# Small_robot_PCB_schematic.net
KiCad netlist of a schematic drawn in EAGLE
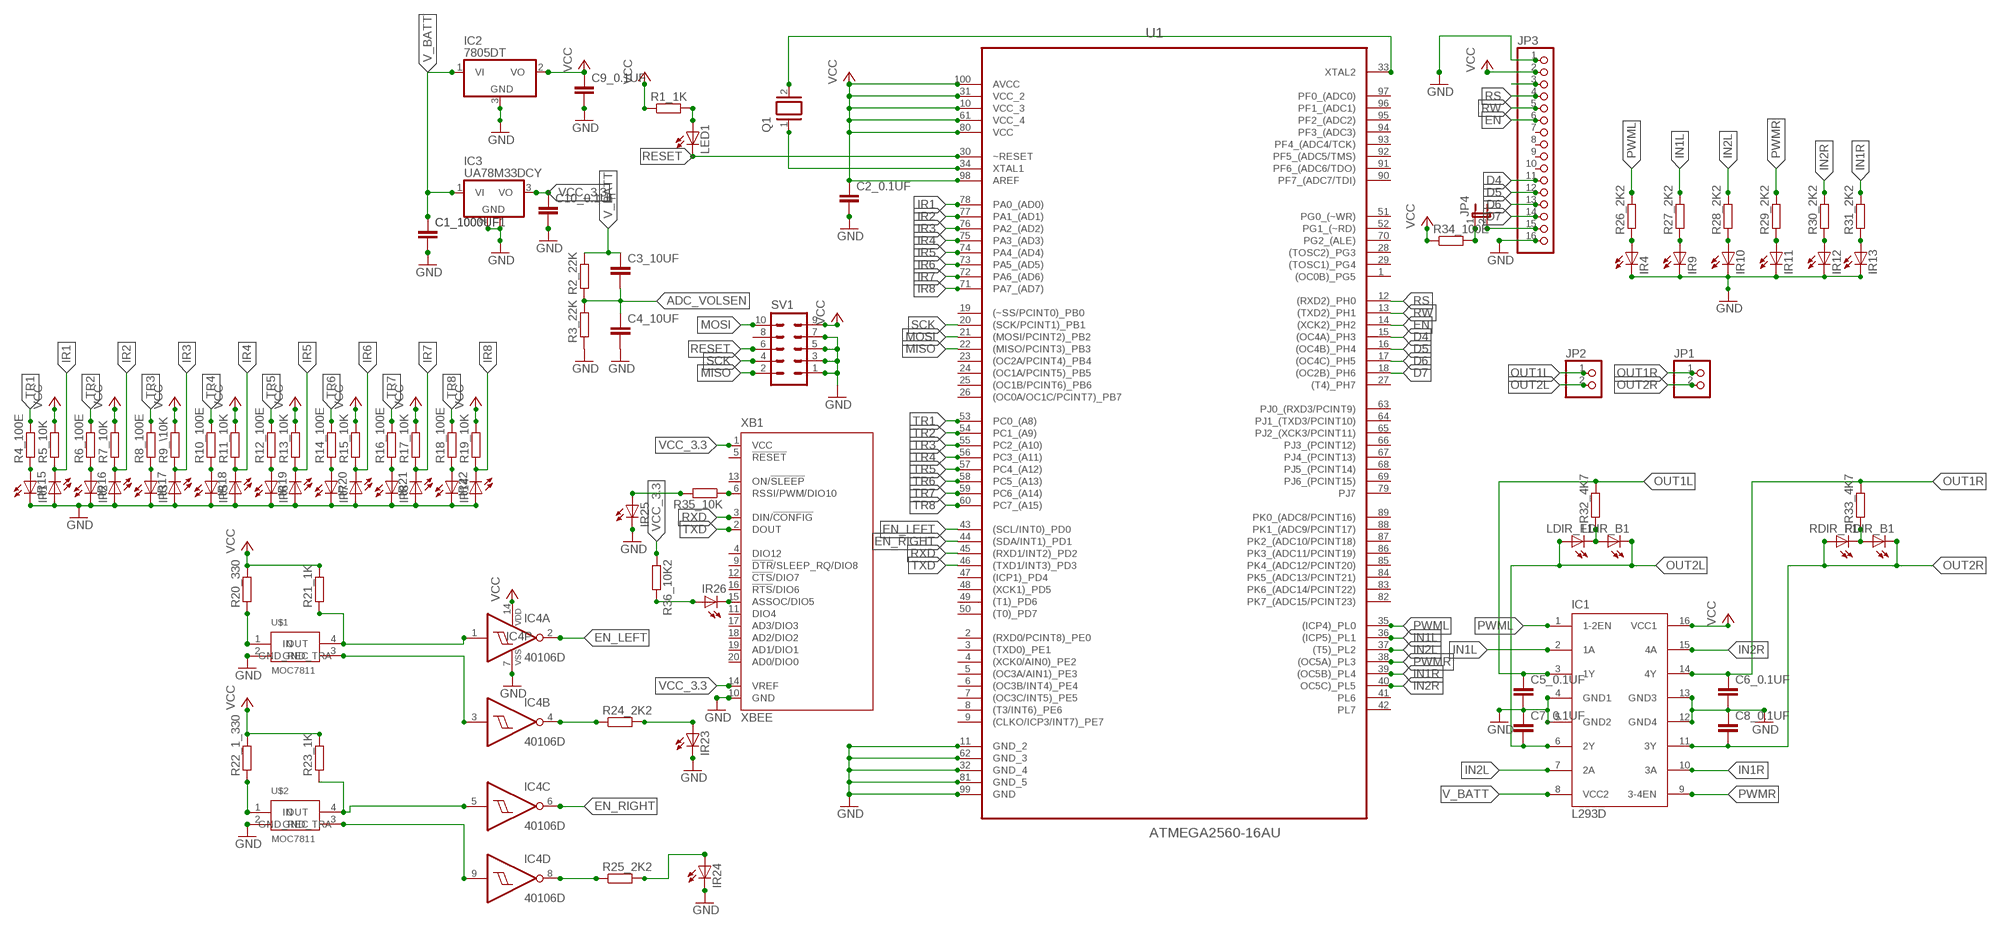
[diagram p0: schematic, sheet 1]

(export (version "E")
  (design (tool "Eeschema 10.0.6"))
  (components
    (comp (ref "C1_1000UF")
      (value "C-EUC1206")
      (footprint "eagle-import:C1206")
      (libsource (lib "eagle-import") (part "resistor_C-EUC1206"))
    )
    (comp (ref "C1_1000UF1")
      (value "C-EUC1206")
      (footprint "eagle-import:C1206")
      (libsource (lib "eagle-import") (part "resistor_C-EUC1206"))
    )
    (comp (ref "C2_0.1UF")
      (value "C-EUC1206")
      (footprint "eagle-import:C1206")
      (libsource (lib "eagle-import") (part "resistor_C-EUC1206"))
    )
    (comp (ref "C3_10UF")
      (value "C-EUC1206")
      (footprint "eagle-import:C1206")
      (libsource (lib "eagle-import") (part "C-EUC1206"))
    )
    (comp (ref "C4_10UF")
      (value "C-EUC1206")
      (footprint "eagle-import:C1206")
      (libsource (lib "eagle-import") (part "C-EUC1206"))
    )
    (comp (ref "C5_0.1UF")
      (value "C-EUC1206")
      (footprint "eagle-import:C1206")
      (libsource (lib "eagle-import") (part "C-EUC1206"))
    )
    (comp (ref "C6_0.1UF")
      (value "C-EUC1206")
      (footprint "eagle-import:C1206")
      (libsource (lib "eagle-import") (part "C-EUC1206"))
    )
    (comp (ref "C7_0.1UF")
      (value "C-EUC1206")
      (footprint "eagle-import:C1206")
      (libsource (lib "eagle-import") (part "C-EUC1206"))
    )
    (comp (ref "C8_0.1UF")
      (value "C-EUC1206")
      (footprint "eagle-import:C1206")
      (libsource (lib "eagle-import") (part "C-EUC1206"))
    )
    (comp (ref "C9_0.1UF")
      (value "C-EUC1206")
      (footprint "eagle-import:C1206")
      (libsource (lib "eagle-import") (part "resistor_C-EUC1206"))
    )
    (comp (ref "C10_0.1UF")
      (value "C-EUC1206")
      (footprint "eagle-import:C1206")
      (libsource (lib "eagle-import") (part "resistor_C-EUC1206"))
    )
    (comp (ref "IC1")
      (value "L293D")
      (footprint "eagle-import:DIL16")
      (libsource (lib "eagle-import") (part "L293D"))
    )
    (comp (ref "IC2")
      (value "7805DT")
      (footprint "eagle-import:TO252")
      (libsource (lib "eagle-import") (part "78DT05"))
    )
    (comp (ref "IC3")
      (value "UA78M33DCY")
      (footprint "eagle-import:SOT223")
      (libsource (lib "eagle-import") (part "UA78MDCY33"))
    )
    (comp (ref "IC4")
      (value "40106D")
      (footprint "eagle-import:SO14")
      (libsource (lib "eagle-import") (part "40106D"))
    )
    (comp (ref "IR1")
      (value "LED5MM")
      (footprint "eagle-import:LED5MM")
      (libsource (lib "eagle-import") (part "LED5MM"))
    )
    (comp (ref "IR2")
      (value "LED5MM")
      (footprint "eagle-import:LED5MM")
      (libsource (lib "eagle-import") (part "LED5MM"))
    )
    (comp (ref "IR3")
      (value "LED5MM")
      (footprint "eagle-import:LED5MM")
      (libsource (lib "eagle-import") (part "LED5MM"))
    )
    (comp (ref "IR4")
      (value "LEDCHIPLED_1206")
      (footprint "eagle-import:CHIPLED_1206")
      (libsource (lib "eagle-import") (part "LEDCHIPLED_1206"))
    )
    (comp (ref "IR5")
      (value "LED5MM")
      (footprint "eagle-import:LED5MM")
      (libsource (lib "eagle-import") (part "LED5MM"))
    )
    (comp (ref "IR6")
      (value "LED5MM")
      (footprint "eagle-import:LED5MM")
      (libsource (lib "eagle-import") (part "LED5MM"))
    )
    (comp (ref "IR7")
      (value "LED5MM")
      (footprint "eagle-import:LED5MM")
      (libsource (lib "eagle-import") (part "LED5MM"))
    )
    (comp (ref "IR8")
      (value "LED5MM")
      (footprint "eagle-import:LED5MM")
      (libsource (lib "eagle-import") (part "LED5MM"))
    )
    (comp (ref "IR9")
      (value "LEDCHIPLED_1206")
      (footprint "eagle-import:CHIPLED_1206")
      (libsource (lib "eagle-import") (part "LEDCHIPLED_1206"))
    )
    (comp (ref "IR10")
      (value "LEDCHIPLED_1206")
      (footprint "eagle-import:CHIPLED_1206")
      (libsource (lib "eagle-import") (part "LEDCHIPLED_1206"))
    )
    (comp (ref "IR11")
      (value "LEDCHIPLED_1206")
      (footprint "eagle-import:CHIPLED_1206")
      (libsource (lib "eagle-import") (part "LEDCHIPLED_1206"))
    )
    (comp (ref "IR12")
      (value "LEDCHIPLED_1206")
      (footprint "eagle-import:CHIPLED_1206")
      (libsource (lib "eagle-import") (part "LEDCHIPLED_1206"))
    )
    (comp (ref "IR13")
      (value "LEDCHIPLED_1206")
      (footprint "eagle-import:CHIPLED_1206")
      (libsource (lib "eagle-import") (part "LEDCHIPLED_1206"))
    )
    (comp (ref "IR14")
      (value "LED5MM")
      (footprint "eagle-import:LED5MM")
      (libsource (lib "eagle-import") (part "LED5MM"))
    )
    (comp (ref "IR15")
      (value "LED5MM")
      (footprint "eagle-import:LED5MM")
      (libsource (lib "eagle-import") (part "LED5MM"))
    )
    (comp (ref "IR16")
      (value "LED5MM")
      (footprint "eagle-import:LED5MM")
      (libsource (lib "eagle-import") (part "LED5MM"))
    )
    (comp (ref "IR17")
      (value "LED5MM")
      (footprint "eagle-import:LED5MM")
      (libsource (lib "eagle-import") (part "LED5MM"))
    )
    (comp (ref "IR18")
      (value "LED5MM")
      (footprint "eagle-import:LED5MM")
      (libsource (lib "eagle-import") (part "LED5MM"))
    )
    (comp (ref "IR19")
      (value "LED5MM")
      (footprint "eagle-import:LED5MM")
      (libsource (lib "eagle-import") (part "LED5MM"))
    )
    (comp (ref "IR20")
      (value "LED5MM")
      (footprint "eagle-import:LED5MM")
      (libsource (lib "eagle-import") (part "LED5MM"))
    )
    (comp (ref "IR21")
      (value "LED5MM")
      (footprint "eagle-import:LED5MM")
      (libsource (lib "eagle-import") (part "LED5MM"))
    )
    (comp (ref "IR22")
      (value "LED5MM")
      (footprint "eagle-import:LED5MM")
      (libsource (lib "eagle-import") (part "LED5MM"))
    )
    (comp (ref "IR23")
      (value "LEDCHIPLED_1206")
      (footprint "eagle-import:CHIPLED_1206")
      (libsource (lib "eagle-import") (part "LEDCHIPLED_1206"))
    )
    (comp (ref "IR24")
      (value "LEDCHIPLED_1206")
      (footprint "eagle-import:CHIPLED_1206")
      (libsource (lib "eagle-import") (part "LEDCHIPLED_1206"))
    )
    (comp (ref "IR25")
      (value "LEDCHIPLED_1206")
      (footprint "eagle-import:CHIPLED_1206")
      (libsource (lib "eagle-import") (part "LEDCHIPLED_1206"))
    )
    (comp (ref "IR26")
      (value "LEDCHIPLED_1206")
      (footprint "eagle-import:CHIPLED_1206")
      (libsource (lib "eagle-import") (part "LEDCHIPLED_1206"))
    )
    (comp (ref "JP1")
      (value "PINHD-1X2")
      (footprint "eagle-import:1X02")
      (libsource (lib "eagle-import") (part "PINHD-1X2"))
    )
    (comp (ref "JP2")
      (value "PINHD-1X2")
      (footprint "eagle-import:1X02")
      (libsource (lib "eagle-import") (part "PINHD-1X2"))
    )
    (comp (ref "JP3")
      (value "PINHD-1X16")
      (footprint "eagle-import:1X16")
      (libsource (lib "eagle-import") (part "PINHD-1X16"))
    )
    (comp (ref "JP4")
      (value "JP1E")
      (footprint "eagle-import:JP1")
      (libsource (lib "eagle-import") (part "JP1E"))
    )
    (comp (ref "LDIR_B1")
      (value "LEDCHIPLED_1206")
      (footprint "eagle-import:CHIPLED_1206")
      (libsource (lib "eagle-import") (part "LEDCHIPLED_1206"))
    )
    (comp (ref "LDIR_F1")
      (value "LEDCHIPLED_1206")
      (footprint "eagle-import:CHIPLED_1206")
      (libsource (lib "eagle-import") (part "LEDCHIPLED_1206"))
    )
    (comp (ref "LED1")
      (value "LEDCHIPLED_1206")
      (footprint "eagle-import:CHIPLED_1206")
      (libsource (lib "eagle-import") (part "LEDCHIPLED_1206"))
    )
    (comp (ref "Q1")
      (value "XTAL")
      (footprint "eagle-import:Q")
      (libsource (lib "eagle-import") (part "XTAL"))
    )
    (comp (ref "R1_1K")
      (value "R-EU_R1206")
      (footprint "eagle-import:R1206")
      (libsource (lib "eagle-import") (part "R-EU_R1206"))
    )
    (comp (ref "R2_22K")
      (value "R-EU_R1206")
      (footprint "eagle-import:R1206")
      (libsource (lib "eagle-import") (part "R-EU_R1206"))
    )
    (comp (ref "R3_22K")
      (value "R-EU_M1206")
      (footprint "eagle-import:M1206")
      (libsource (lib "eagle-import") (part "R-EU_M1206"))
    )
    (comp (ref "R4_100E")
      (value "R-EU_R1206")
      (footprint "eagle-import:R1206")
      (libsource (lib "eagle-import") (part "R-EU_R1206"))
    )
    (comp (ref "R5_10K")
      (value "R-EU_R1206")
      (footprint "eagle-import:R1206")
      (libsource (lib "eagle-import") (part "R-EU_R1206"))
    )
    (comp (ref "R6_100E")
      (value "R-EU_R1206")
      (footprint "eagle-import:R1206")
      (libsource (lib "eagle-import") (part "R-EU_R1206"))
    )
    (comp (ref "R7_10K")
      (value "R-EU_R1206")
      (footprint "eagle-import:R1206")
      (libsource (lib "eagle-import") (part "R-EU_R1206"))
    )
    (comp (ref "R8_100E")
      (value "R-EU_R1206")
      (footprint "eagle-import:R1206")
      (libsource (lib "eagle-import") (part "R-EU_R1206"))
    )
    (comp (ref "R9_\\10K")
      (value "R-EU_R1206")
      (footprint "eagle-import:R1206")
      (libsource (lib "eagle-import") (part "R-EU_R1206"))
    )
    (comp (ref "R10_100E")
      (value "R-EU_R1206")
      (footprint "eagle-import:R1206")
      (libsource (lib "eagle-import") (part "R-EU_R1206"))
    )
    (comp (ref "R11_10K")
      (value "R-EU_R1206")
      (footprint "eagle-import:R1206")
      (libsource (lib "eagle-import") (part "R-EU_R1206"))
    )
    (comp (ref "R12_100E")
      (value "R-EU_R1206")
      (footprint "eagle-import:R1206")
      (libsource (lib "eagle-import") (part "R-EU_R1206"))
    )
    (comp (ref "R13_10K")
      (value "R-EU_R1206")
      (footprint "eagle-import:R1206")
      (libsource (lib "eagle-import") (part "R-EU_R1206"))
    )
    (comp (ref "R14_100E")
      (value "R-EU_R1206")
      (footprint "eagle-import:R1206")
      (libsource (lib "eagle-import") (part "R-EU_R1206"))
    )
    (comp (ref "R15_10K")
      (value "R-EU_R1206")
      (footprint "eagle-import:R1206")
      (libsource (lib "eagle-import") (part "R-EU_R1206"))
    )
    (comp (ref "R16_100E")
      (value "R-EU_R1206")
      (footprint "eagle-import:R1206")
      (libsource (lib "eagle-import") (part "R-EU_R1206"))
    )
    (comp (ref "R17_10K")
      (value "R-EU_R1206")
      (footprint "eagle-import:R1206")
      (libsource (lib "eagle-import") (part "R-EU_R1206"))
    )
    (comp (ref "R18_100E")
      (value "R-EU_R1206")
      (footprint "eagle-import:R1206")
      (libsource (lib "eagle-import") (part "R-EU_R1206"))
    )
    (comp (ref "R19_10K")
      (value "R-EU_R1206")
      (footprint "eagle-import:R1206")
      (libsource (lib "eagle-import") (part "R-EU_R1206"))
    )
    (comp (ref "R20_330")
      (value "R-EU_R1206")
      (footprint "eagle-import:R1206")
      (libsource (lib "eagle-import") (part "R-EU_R1206"))
    )
    (comp (ref "R21_1K")
      (value "R-EU_R1206")
      (footprint "eagle-import:R1206")
      (libsource (lib "eagle-import") (part "R-EU_R1206"))
    )
    (comp (ref "R22_1_330")
      (value "R-EU_R1206")
      (footprint "eagle-import:R1206")
      (libsource (lib "eagle-import") (part "R-EU_R1206"))
    )
    (comp (ref "R23_1K")
      (value "R-EU_R1206")
      (footprint "eagle-import:R1206")
      (libsource (lib "eagle-import") (part "R-EU_R1206"))
    )
    (comp (ref "R24_2K2")
      (value "R-EU_R1206")
      (footprint "eagle-import:R1206")
      (libsource (lib "eagle-import") (part "R-EU_R1206"))
    )
    (comp (ref "R25_2K2")
      (value "R-EU_R1206")
      (footprint "eagle-import:R1206")
      (libsource (lib "eagle-import") (part "R-EU_R1206"))
    )
    (comp (ref "R26_2K2")
      (value "R-EU_R1206")
      (footprint "eagle-import:R1206")
      (libsource (lib "eagle-import") (part "R-EU_R1206"))
    )
    (comp (ref "R27_2K2")
      (value "R-EU_R1206")
      (footprint "eagle-import:R1206")
      (libsource (lib "eagle-import") (part "R-EU_R1206"))
    )
    (comp (ref "R28_2K2")
      (value "R-EU_R1206")
      (footprint "eagle-import:R1206")
      (libsource (lib "eagle-import") (part "R-EU_R1206"))
    )
    (comp (ref "R29_2K2")
      (value "R-EU_R1206")
      (footprint "eagle-import:R1206")
      (libsource (lib "eagle-import") (part "R-EU_R1206"))
    )
    (comp (ref "R30_2K2")
      (value "R-EU_R1206")
      (footprint "eagle-import:R1206")
      (libsource (lib "eagle-import") (part "R-EU_R1206"))
    )
    (comp (ref "R31_2K2")
      (value "R-EU_R1206")
      (footprint "eagle-import:R1206")
      (libsource (lib "eagle-import") (part "R-EU_R1206"))
    )
    (comp (ref "R32_4K7")
      (value "R-EU_R1206")
      (footprint "eagle-import:R1206")
      (libsource (lib "eagle-import") (part "R-EU_R1206"))
    )
    (comp (ref "R33_4K7")
      (value "R-EU_R1206")
      (footprint "eagle-import:R1206")
      (libsource (lib "eagle-import") (part "R-EU_R1206"))
    )
    (comp (ref "R34_100E")
      (value "R-EU_R1206")
      (footprint "eagle-import:R1206")
      (libsource (lib "eagle-import") (part "R-EU_R1206"))
    )
    (comp (ref "R35_10K")
      (value "R-EU_R1206")
      (footprint "eagle-import:R1206")
      (libsource (lib "eagle-import") (part "R-EU_R1206"))
    )
    (comp (ref "R36_10K2")
      (value "R-EU_R1206")
      (footprint "eagle-import:R1206")
      (libsource (lib "eagle-import") (part "R-EU_R1206"))
    )
    (comp (ref "RDIR_B1")
      (value "LEDCHIPLED_1206")
      (footprint "eagle-import:CHIPLED_1206")
      (libsource (lib "eagle-import") (part "LEDCHIPLED_1206"))
    )
    (comp (ref "RDIR_F1")
      (value "LEDCHIPLED_1206")
      (footprint "eagle-import:CHIPLED_1206")
      (libsource (lib "eagle-import") (part "LEDCHIPLED_1206"))
    )
    (comp (ref "SV1")
      (value "MA05-2")
      (footprint "eagle-import:MA05-2")
      (libsource (lib "eagle-import") (part "MA05-2"))
    )
    (comp (ref "U$1")
      (value "MOC7811")
      (footprint "eagle-import:THROUGH_HOLE_NORMAL")
      (libsource (lib "eagle-import") (part "MOC7811"))
    )
    (comp (ref "U$2")
      (value "MOC7811")
      (footprint "eagle-import:THROUGH_HOLE_NORMAL")
      (libsource (lib "eagle-import") (part "MOC7811"))
    )
    (comp (ref "U1")
      (value "ATMEGA2560-16AU")
      (footprint "eagle-import:QFP50P1600X1600X120-100N")
      (libsource (lib "eagle-import") (part "ATMEGA2560-16AU"))
    )
    (comp (ref "XB1")
      (value "XBEE")
      (footprint "eagle-import:XBEE")
      (fields (field (name "MPN") "XBP24-Z7UIT-004"))
      (libsource (lib "eagle-import") (part "XBEE"))
    )
  )
  (nets
    (net (code "1") (name "ADC_VOLSEN") (class "Default")
      (node (ref "C3_10UF") (pin "2") (pinfunction "2_2") (pintype "passive"))
      (node (ref "C4_10UF") (pin "1") (pinfunction "1_1") (pintype "passive"))
      (node (ref "R2_22K") (pin "1") (pinfunction "1_1") (pintype "passive"))
      (node (ref "R3_22K") (pin "2") (pinfunction "2_2") (pintype "passive"))
    )
    (net (code "2") (name "D4") (class "Default")
      (node (ref "JP3") (pin "11") (pinfunction "11_11") (pintype "passive"))
      (node (ref "U1") (pin "15") (pinfunction "(OC4A)_PH3_15") (pintype "bidirectional"))
    )
    (net (code "3") (name "D5") (class "Default")
      (node (ref "JP3") (pin "12") (pinfunction "12_12") (pintype "passive"))
      (node (ref "U1") (pin "16") (pinfunction "(OC4B)_PH4_16") (pintype "bidirectional"))
    )
    (net (code "4") (name "D6") (class "Default")
      (node (ref "JP3") (pin "13") (pinfunction "13_13") (pintype "passive"))
      (node (ref "U1") (pin "17") (pinfunction "(OC4C)_PH5_17") (pintype "bidirectional"))
    )
    (net (code "5") (name "D7") (class "Default")
      (node (ref "JP3") (pin "14") (pinfunction "14_14") (pintype "passive"))
      (node (ref "U1") (pin "18") (pinfunction "(OC2B)_PH6_18") (pintype "bidirectional"))
    )
    (net (code "6") (name "EN") (class "Default")
      (node (ref "JP3") (pin "6") (pinfunction "6_6") (pintype "passive"))
      (node (ref "U1") (pin "14") (pinfunction "(XCK2)_PH2_14") (pintype "bidirectional"))
    )
    (net (code "7") (name "EN_LEFT") (class "Default")
      (node (ref "IC4") (pin "2") (pinfunction "O_2") (pintype "output"))
      (node (ref "U1") (pin "43") (pinfunction "(SCL/INT0)_PD0_43") (pintype "bidirectional"))
    )
    (net (code "8") (name "EN_RIGHT") (class "Default")
      (node (ref "IC4") (pin "6") (pinfunction "O_6") (pintype "output"))
      (node (ref "U1") (pin "44") (pinfunction "(SDA/INT1)_PD1_44") (pintype "bidirectional"))
    )
    (net (code "9") (name "GND") (class "Default")
      (node (ref "C10_0.1UF") (pin "2") (pinfunction "2_2") (pintype "passive"))
      (node (ref "C1_1000UF") (pin "2") (pinfunction "2_2") (pintype "passive"))
      (node (ref "C1_1000UF1") (pin "2") (pinfunction "2_2") (pintype "passive"))
      (node (ref "C2_0.1UF") (pin "2") (pinfunction "2_2") (pintype "passive"))
      (node (ref "C4_10UF") (pin "2") (pinfunction "2_2") (pintype "passive"))
      (node (ref "C5_0.1UF") (pin "2") (pinfunction "2_2") (pintype "passive"))
      (node (ref "C6_0.1UF") (pin "2") (pinfunction "2_2") (pintype "passive"))
      (node (ref "C7_0.1UF") (pin "1") (pinfunction "1_1") (pintype "passive"))
      (node (ref "C8_0.1UF") (pin "1") (pinfunction "1_1") (pintype "passive"))
      (node (ref "C9_0.1UF") (pin "2") (pinfunction "2_2") (pintype "passive"))
      (node (ref "IC1") (pin "12") (pinfunction "GND4_12") (pintype "power_in"))
      (node (ref "IC1") (pin "13") (pinfunction "GND3_13") (pintype "power_in"))
      (node (ref "IC1") (pin "4") (pinfunction "GND1_4") (pintype "power_in"))
      (node (ref "IC1") (pin "5") (pinfunction "GND2_5") (pintype "power_in"))
      (node (ref "IC2") (pin "3") (pinfunction "GND_3") (pintype "passive"))
      (node (ref "IC3") (pin "2") (pinfunction "GND_2") (pintype "passive"))
      (node (ref "IC3") (pin "4") (pinfunction "GND_4") (pintype "passive"))
      (node (ref "IC4") (pin "7") (pinfunction "VSS_7") (pintype "power_in"))
      (node (ref "IR1") (pin "K") (pinfunction "C_K") (pintype "passive"))
      (node (ref "IR10") (pin "C") (pinfunction "C_C") (pintype "passive"))
      (node (ref "IR11") (pin "C") (pinfunction "C_C") (pintype "passive"))
      (node (ref "IR12") (pin "C") (pinfunction "C_C") (pintype "passive"))
      (node (ref "IR13") (pin "C") (pinfunction "C_C") (pintype "passive"))
      (node (ref "IR14") (pin "K") (pinfunction "C_K") (pintype "passive"))
      (node (ref "IR15") (pin "A") (pinfunction "A_A") (pintype "passive"))
      (node (ref "IR16") (pin "A") (pinfunction "A_A") (pintype "passive"))
      (node (ref "IR17") (pin "A") (pinfunction "A_A") (pintype "passive"))
      (node (ref "IR18") (pin "A") (pinfunction "A_A") (pintype "passive"))
      (node (ref "IR19") (pin "A") (pinfunction "A_A") (pintype "passive"))
      (node (ref "IR2") (pin "K") (pinfunction "C_K") (pintype "passive"))
      (node (ref "IR20") (pin "A") (pinfunction "A_A") (pintype "passive"))
      (node (ref "IR21") (pin "A") (pinfunction "A_A") (pintype "passive"))
      (node (ref "IR22") (pin "A") (pinfunction "A_A") (pintype "passive"))
      (node (ref "IR23") (pin "C") (pinfunction "C_C") (pintype "passive"))
      (node (ref "IR24") (pin "C") (pinfunction "C_C") (pintype "passive"))
      (node (ref "IR25") (pin "C") (pinfunction "C_C") (pintype "passive"))
      (node (ref "IR3") (pin "K") (pinfunction "C_K") (pintype "passive"))
      (node (ref "IR4") (pin "C") (pinfunction "C_C") (pintype "passive"))
      (node (ref "IR5") (pin "K") (pinfunction "C_K") (pintype "passive"))
      (node (ref "IR6") (pin "K") (pinfunction "C_K") (pintype "passive"))
      (node (ref "IR7") (pin "K") (pinfunction "C_K") (pintype "passive"))
      (node (ref "IR8") (pin "K") (pinfunction "C_K") (pintype "passive"))
      (node (ref "IR9") (pin "C") (pinfunction "C_C") (pintype "passive"))
      (node (ref "JP3") (pin "1") (pinfunction "1_1") (pintype "passive"))
      (node (ref "JP3") (pin "16") (pinfunction "16_16") (pintype "passive"))
      (node (ref "R3_22K") (pin "1") (pinfunction "1_1") (pintype "passive"))
      (node (ref "SV1") (pin "1") (pinfunction "1_1") (pintype "passive"))
      (node (ref "SV1") (pin "3") (pinfunction "3_3") (pintype "passive"))
      (node (ref "SV1") (pin "5") (pinfunction "5_5") (pintype "passive"))
      (node (ref "SV1") (pin "7") (pinfunction "7_7") (pintype "passive"))
      (node (ref "U$1") (pin "2") (pinfunction "GND_TRA_2") (pintype "bidirectional"))
      (node (ref "U$2") (pin "2") (pinfunction "GND_TRA_2") (pintype "bidirectional"))
      (node (ref "U1") (pin "11") (pinfunction "GND_2_11") (pintype "passive"))
      (node (ref "U1") (pin "32") (pinfunction "GND_4_32") (pintype "passive"))
      (node (ref "U1") (pin "62") (pinfunction "GND_3_62") (pintype "passive"))
      (node (ref "U1") (pin "81") (pinfunction "GND_5_81") (pintype "passive"))
      (node (ref "U1") (pin "99") (pinfunction "GND_99") (pintype "passive"))
      (node (ref "XB1") (pin "10") (pinfunction "GND_10") (pintype "power_in"))
    )
    (net (code "10") (name "IN1L") (class "Default")
      (node (ref "IC1") (pin "2") (pinfunction "1A_2") (pintype "input"))
      (node (ref "R27_2K2") (pin "2") (pinfunction "2_2") (pintype "passive"))
      (node (ref "U1") (pin "36") (pinfunction "(ICP5)_PL1_36") (pintype "bidirectional"))
    )
    (net (code "11") (name "IN1R") (class "Default")
      (node (ref "IC1") (pin "10") (pinfunction "3A_10") (pintype "input"))
      (node (ref "R31_2K2") (pin "2") (pinfunction "2_2") (pintype "passive"))
      (node (ref "U1") (pin "39") (pinfunction "(OC5B)_PL4_39") (pintype "bidirectional"))
    )
    (net (code "12") (name "IN2L") (class "Default")
      (node (ref "IC1") (pin "7") (pinfunction "2A_7") (pintype "input"))
      (node (ref "R28_2K2") (pin "2") (pinfunction "2_2") (pintype "passive"))
      (node (ref "U1") (pin "37") (pinfunction "(T5)_PL2_37") (pintype "bidirectional"))
    )
    (net (code "13") (name "IN2R") (class "Default")
      (node (ref "IC1") (pin "15") (pinfunction "4A_15") (pintype "input"))
      (node (ref "R30_2K2") (pin "2") (pinfunction "2_2") (pintype "passive"))
      (node (ref "U1") (pin "40") (pinfunction "OC5C)_PL5_40") (pintype "bidirectional"))
    )
    (net (code "14") (name "IR1") (class "Default")
      (node (ref "IR15") (pin "K") (pinfunction "C_K") (pintype "passive"))
      (node (ref "R5_10K") (pin "1") (pinfunction "1_1") (pintype "passive"))
      (node (ref "U1") (pin "78") (pinfunction "PA0_(AD0)_78") (pintype "bidirectional"))
    )
    (net (code "15") (name "IR2") (class "Default")
      (node (ref "IR16") (pin "K") (pinfunction "C_K") (pintype "passive"))
      (node (ref "R7_10K") (pin "1") (pinfunction "1_1") (pintype "passive"))
      (node (ref "U1") (pin "77") (pinfunction "PA1_(AD1)_77") (pintype "bidirectional"))
    )
    (net (code "16") (name "IR3") (class "Default")
      (node (ref "IR17") (pin "K") (pinfunction "C_K") (pintype "passive"))
      (node (ref "R9_\\10K") (pin "1") (pinfunction "1_1") (pintype "passive"))
      (node (ref "U1") (pin "76") (pinfunction "PA2_(AD2)_76") (pintype "bidirectional"))
    )
    (net (code "17") (name "IR4") (class "Default")
      (node (ref "IR18") (pin "K") (pinfunction "C_K") (pintype "passive"))
      (node (ref "R11_10K") (pin "1") (pinfunction "1_1") (pintype "passive"))
      (node (ref "U1") (pin "75") (pinfunction "PA3_(AD3)_75") (pintype "bidirectional"))
    )
    (net (code "18") (name "IR5") (class "Default")
      (node (ref "IR19") (pin "K") (pinfunction "C_K") (pintype "passive"))
      (node (ref "R13_10K") (pin "1") (pinfunction "1_1") (pintype "passive"))
      (node (ref "U1") (pin "74") (pinfunction "PA4_(AD4)_74") (pintype "bidirectional"))
    )
    (net (code "19") (name "IR6") (class "Default")
      (node (ref "IR20") (pin "K") (pinfunction "C_K") (pintype "passive"))
      (node (ref "R15_10K") (pin "1") (pinfunction "1_1") (pintype "passive"))
      (node (ref "U1") (pin "73") (pinfunction "PA5_(AD5)_73") (pintype "bidirectional"))
    )
    (net (code "20") (name "IR7") (class "Default")
      (node (ref "IR21") (pin "K") (pinfunction "C_K") (pintype "passive"))
      (node (ref "R17_10K") (pin "1") (pinfunction "1_1") (pintype "passive"))
      (node (ref "U1") (pin "72") (pinfunction "PA6_(AD6)_72") (pintype "bidirectional"))
    )
    (net (code "21") (name "IR8") (class "Default")
      (node (ref "IR22") (pin "K") (pinfunction "C_K") (pintype "passive"))
      (node (ref "R19_10K") (pin "1") (pinfunction "1_1") (pintype "passive"))
      (node (ref "U1") (pin "71") (pinfunction "PA7_(AD7)_71") (pintype "bidirectional"))
    )
    (net (code "22") (name "MISO") (class "Default")
      (node (ref "SV1") (pin "2") (pinfunction "2_2") (pintype "passive"))
      (node (ref "U1") (pin "22") (pinfunction "(MISO/PCINT3)_PB3_22") (pintype "bidirectional"))
    )
    (net (code "23") (name "MOSI") (class "Default")
      (node (ref "SV1") (pin "10") (pinfunction "10_10") (pintype "passive"))
      (node (ref "U1") (pin "21") (pinfunction "(MOSI/PCINT2)_PB2_21") (pintype "bidirectional"))
    )
    (net (code "24") (name "Net-(IC4A-I)") (class "Default")
      (node (ref "IC4") (pin "1") (pinfunction "I_1") (pintype "input"))
      (node (ref "R21_1K") (pin "1") (pinfunction "1_1") (pintype "passive"))
      (node (ref "U$1") (pin "4") (pinfunction "OUT_4") (pintype "bidirectional"))
    )
    (net (code "25") (name "Net-(IC4B-I)") (class "Default")
      (node (ref "IC4") (pin "3") (pinfunction "I_3") (pintype "input"))
      (node (ref "U$1") (pin "3") (pinfunction "GND_REC_3") (pintype "bidirectional"))
    )
    (net (code "26") (name "Net-(IC4B-O)") (class "Default")
      (node (ref "IC4") (pin "4") (pinfunction "O_4") (pintype "output"))
      (node (ref "R24_2K2") (pin "1") (pinfunction "1_1") (pintype "passive"))
    )
    (net (code "27") (name "Net-(IC4C-I)") (class "Default")
      (node (ref "IC4") (pin "5") (pinfunction "I_5") (pintype "input"))
      (node (ref "R23_1K") (pin "1") (pinfunction "1_1") (pintype "passive"))
      (node (ref "U$2") (pin "4") (pinfunction "OUT_4") (pintype "bidirectional"))
    )
    (net (code "28") (name "Net-(IC4D-I)") (class "Default")
      (node (ref "IC4") (pin "9") (pinfunction "I_9") (pintype "input"))
      (node (ref "U$2") (pin "3") (pinfunction "GND_REC_3") (pintype "bidirectional"))
    )
    (net (code "29") (name "Net-(IC4D-O)") (class "Default")
      (node (ref "IC4") (pin "8") (pinfunction "O_8") (pintype "output"))
      (node (ref "R25_2K2") (pin "1") (pinfunction "1_1") (pintype "passive"))
    )
    (net (code "30") (name "Net-(IR1-PadA)") (class "Default")
      (node (ref "IR1") (pin "A") (pinfunction "A_A") (pintype "passive"))
      (node (ref "R4_100E") (pin "1") (pinfunction "1_1") (pintype "passive"))
    )
    (net (code "31") (name "Net-(IR2-PadA)") (class "Default")
      (node (ref "IR2") (pin "A") (pinfunction "A_A") (pintype "passive"))
      (node (ref "R6_100E") (pin "1") (pinfunction "1_1") (pintype "passive"))
    )
    (net (code "32") (name "Net-(IR3-PadA)") (class "Default")
      (node (ref "IR3") (pin "A") (pinfunction "A_A") (pintype "passive"))
      (node (ref "R8_100E") (pin "1") (pinfunction "1_1") (pintype "passive"))
    )
    (net (code "33") (name "Net-(IR4-PadA)") (class "Default")
      (node (ref "IR4") (pin "A") (pinfunction "A_A") (pintype "passive"))
      (node (ref "R26_2K2") (pin "1") (pinfunction "1_1") (pintype "passive"))
    )
    (net (code "34") (name "Net-(IR5-PadA)") (class "Default")
      (node (ref "IR5") (pin "A") (pinfunction "A_A") (pintype "passive"))
      (node (ref "R10_100E") (pin "1") (pinfunction "1_1") (pintype "passive"))
    )
    (net (code "35") (name "Net-(IR6-PadA)") (class "Default")
      (node (ref "IR6") (pin "A") (pinfunction "A_A") (pintype "passive"))
      (node (ref "R12_100E") (pin "1") (pinfunction "1_1") (pintype "passive"))
    )
    (net (code "36") (name "Net-(IR7-PadA)") (class "Default")
      (node (ref "IR7") (pin "A") (pinfunction "A_A") (pintype "passive"))
      (node (ref "R14_100E") (pin "1") (pinfunction "1_1") (pintype "passive"))
    )
    (net (code "37") (name "Net-(IR8-PadA)") (class "Default")
      (node (ref "IR8") (pin "A") (pinfunction "A_A") (pintype "passive"))
      (node (ref "R16_100E") (pin "1") (pinfunction "1_1") (pintype "passive"))
    )
    (net (code "38") (name "Net-(IR9-PadA)") (class "Default")
      (node (ref "IR9") (pin "A") (pinfunction "A_A") (pintype "passive"))
      (node (ref "R27_2K2") (pin "1") (pinfunction "1_1") (pintype "passive"))
    )
    (net (code "39") (name "Net-(IR10-PadA)") (class "Default")
      (node (ref "IR10") (pin "A") (pinfunction "A_A") (pintype "passive"))
      (node (ref "R28_2K2") (pin "1") (pinfunction "1_1") (pintype "passive"))
    )
    (net (code "40") (name "Net-(IR11-PadA)") (class "Default")
      (node (ref "IR11") (pin "A") (pinfunction "A_A") (pintype "passive"))
      (node (ref "R29_2K2") (pin "1") (pinfunction "1_1") (pintype "passive"))
    )
    (net (code "41") (name "Net-(IR12-PadA)") (class "Default")
      (node (ref "IR12") (pin "A") (pinfunction "A_A") (pintype "passive"))
      (node (ref "R30_2K2") (pin "1") (pinfunction "1_1") (pintype "passive"))
    )
    (net (code "42") (name "Net-(IR13-PadA)") (class "Default")
      (node (ref "IR13") (pin "A") (pinfunction "A_A") (pintype "passive"))
      (node (ref "R31_2K2") (pin "1") (pinfunction "1_1") (pintype "passive"))
    )
    (net (code "43") (name "Net-(IR14-PadA)") (class "Default")
      (node (ref "IR14") (pin "A") (pinfunction "A_A") (pintype "passive"))
      (node (ref "R18_100E") (pin "1") (pinfunction "1_1") (pintype "passive"))
    )
    (net (code "44") (name "Net-(IR23-PadA)") (class "Default")
      (node (ref "IR23") (pin "A") (pinfunction "A_A") (pintype "passive"))
      (node (ref "R24_2K2") (pin "2") (pinfunction "2_2") (pintype "passive"))
    )
    (net (code "45") (name "Net-(IR24-PadA)") (class "Default")
      (node (ref "IR24") (pin "A") (pinfunction "A_A") (pintype "passive"))
      (node (ref "R25_2K2") (pin "2") (pinfunction "2_2") (pintype "passive"))
    )
    (net (code "46") (name "Net-(IR25-PadA)") (class "Default")
      (node (ref "IR25") (pin "A") (pinfunction "A_A") (pintype "passive"))
      (node (ref "R35_10K") (pin "2") (pinfunction "2_2") (pintype "passive"))
    )
    (net (code "47") (name "Net-(IR26-PadA)") (class "Default")
      (node (ref "IR26") (pin "A") (pinfunction "A_A") (pintype "passive"))
      (node (ref "R36_10K2") (pin "2") (pinfunction "2_2") (pintype "passive"))
    )
    (net (code "48") (name "Net-(JP3-Pad15)") (class "Default")
      (node (ref "JP3") (pin "15") (pinfunction "15_15") (pintype "passive"))
      (node (ref "JP4") (pin "2") (pinfunction "2_2") (pintype "passive"))
    )
    (net (code "49") (name "Net-(JP4-Pad1)") (class "Default")
      (node (ref "JP4") (pin "1") (pinfunction "1_1") (pintype "passive"))
      (node (ref "R34_100E") (pin "2") (pinfunction "2_2") (pintype "passive"))
    )
    (net (code "50") (name "Net-(LDIR_B1-PadA)") (class "Default")
      (node (ref "LDIR_B1") (pin "A") (pinfunction "A_A") (pintype "passive"))
      (node (ref "LDIR_F1") (pin "C") (pinfunction "C_C") (pintype "passive"))
      (node (ref "R32_4K7") (pin "1") (pinfunction "1_1") (pintype "passive"))
    )
    (net (code "51") (name "Net-(LED1-PadA)") (class "Default")
      (node (ref "LED1") (pin "A") (pinfunction "A_A") (pintype "passive"))
      (node (ref "R1_1K") (pin "2") (pinfunction "2_2") (pintype "passive"))
    )
    (net (code "52") (name "Net-(R33_4K7-Pad1)") (class "Default")
      (node (ref "R33_4K7") (pin "1") (pinfunction "1_1") (pintype "passive"))
      (node (ref "RDIR_B1") (pin "A") (pinfunction "A_A") (pintype "passive"))
      (node (ref "RDIR_F1") (pin "C") (pinfunction "C_C") (pintype "passive"))
    )
    (net (code "53") (name "Net-(U$1-IN)") (class "Default")
      (node (ref "R20_330") (pin "1") (pinfunction "1_1") (pintype "passive"))
      (node (ref "U$1") (pin "1") (pinfunction "IN_1") (pintype "bidirectional"))
    )
    (net (code "54") (name "Net-(U$2-IN)") (class "Default")
      (node (ref "R22_1_330") (pin "1") (pinfunction "1_1") (pintype "passive"))
      (node (ref "U$2") (pin "1") (pinfunction "IN_1") (pintype "bidirectional"))
    )
    (net (code "55") (name "Net-(U1-XTAL1)") (class "Default")
      (node (ref "Q1") (pin "1") (pinfunction "1_1") (pintype "passive"))
      (node (ref "U1") (pin "34") (pinfunction "XTAL1_34") (pintype "input"))
    )
    (net (code "56") (name "Net-(U1-XTAL2)") (class "Default")
      (node (ref "Q1") (pin "2") (pinfunction "2_2") (pintype "passive"))
      (node (ref "U1") (pin "33") (pinfunction "XTAL2_33") (pintype "output"))
    )
    (net (code "57") (name "Net-(XB1-ASSOC{slash}DIO5)") (class "Default")
      (node (ref "IR26") (pin "C") (pinfunction "C_C") (pintype "passive"))
      (node (ref "XB1") (pin "15") (pinfunction "ASSOC/DIO5_15") (pintype "bidirectional"))
    )
    (net (code "58") (name "Net-(XB1-RSSI{slash}PWM{slash}DIO10)") (class "Default")
      (node (ref "R35_10K") (pin "1") (pinfunction "1_1") (pintype "passive"))
      (node (ref "XB1") (pin "6") (pinfunction "RSSI/PWM/DIO10_6") (pintype "output"))
    )
    (net (code "59") (name "OUT1L") (class "Default")
      (node (ref "C5_0.1UF") (pin "1") (pinfunction "1_1") (pintype "passive"))
      (node (ref "IC1") (pin "3") (pinfunction "1Y_3") (pintype "output"))
      (node (ref "JP2") (pin "1") (pinfunction "1_1") (pintype "passive"))
      (node (ref "R32_4K7") (pin "2") (pinfunction "2_2") (pintype "passive"))
    )
    (net (code "60") (name "OUT1R") (class "Default")
      (node (ref "C6_0.1UF") (pin "1") (pinfunction "1_1") (pintype "passive"))
      (node (ref "IC1") (pin "14") (pinfunction "4Y_14") (pintype "output"))
      (node (ref "JP1") (pin "1") (pinfunction "1_1") (pintype "passive"))
      (node (ref "R33_4K7") (pin "2") (pinfunction "2_2") (pintype "passive"))
    )
    (net (code "61") (name "OUT2L") (class "Default")
      (node (ref "C7_0.1UF") (pin "2") (pinfunction "2_2") (pintype "passive"))
      (node (ref "IC1") (pin "6") (pinfunction "2Y_6") (pintype "output"))
      (node (ref "JP2") (pin "2") (pinfunction "2_2") (pintype "passive"))
      (node (ref "LDIR_B1") (pin "C") (pinfunction "C_C") (pintype "passive"))
      (node (ref "LDIR_F1") (pin "A") (pinfunction "A_A") (pintype "passive"))
    )
    (net (code "62") (name "OUT2R") (class "Default")
      (node (ref "C8_0.1UF") (pin "2") (pinfunction "2_2") (pintype "passive"))
      (node (ref "IC1") (pin "11") (pinfunction "3Y_11") (pintype "output"))
      (node (ref "JP1") (pin "2") (pinfunction "2_2") (pintype "passive"))
      (node (ref "RDIR_B1") (pin "C") (pinfunction "C_C") (pintype "passive"))
      (node (ref "RDIR_F1") (pin "A") (pinfunction "A_A") (pintype "passive"))
    )
    (net (code "63") (name "PWML") (class "Default")
      (node (ref "IC1") (pin "1") (pinfunction "1-2EN_1") (pintype "input"))
      (node (ref "R26_2K2") (pin "2") (pinfunction "2_2") (pintype "passive"))
      (node (ref "U1") (pin "35") (pinfunction "(ICP4)_PL0_35") (pintype "bidirectional"))
    )
    (net (code "64") (name "PWMR") (class "Default")
      (node (ref "IC1") (pin "9") (pinfunction "3-4EN_9") (pintype "input"))
      (node (ref "R29_2K2") (pin "2") (pinfunction "2_2") (pintype "passive"))
      (node (ref "U1") (pin "38") (pinfunction "(OC5A)_PL3_38") (pintype "bidirectional"))
    )
    (net (code "65") (name "RESET") (class "Default")
      (node (ref "LED1") (pin "C") (pinfunction "C_C") (pintype "passive"))
      (node (ref "SV1") (pin "6") (pinfunction "6_6") (pintype "passive"))
      (node (ref "U1") (pin "30") (pinfunction "~{RESET}_30") (pintype "input"))
    )
    (net (code "66") (name "RS") (class "Default")
      (node (ref "JP3") (pin "4") (pinfunction "4_4") (pintype "passive"))
      (node (ref "U1") (pin "12") (pinfunction "(RXD2)_PH0_12") (pintype "bidirectional"))
    )
    (net (code "67") (name "RW") (class "Default")
      (node (ref "JP3") (pin "5") (pinfunction "5_5") (pintype "passive"))
      (node (ref "U1") (pin "13") (pinfunction "(TXD2)_PH1_13") (pintype "bidirectional"))
    )
    (net (code "68") (name "RXD") (class "Default")
      (node (ref "U1") (pin "45") (pinfunction "(RXD1/INT2)_PD2_45") (pintype "bidirectional"))
      (node (ref "XB1") (pin "3") (pinfunction "DIN/~{CONFIG}_3") (pintype "input"))
    )
    (net (code "69") (name "SCK") (class "Default")
      (node (ref "SV1") (pin "4") (pinfunction "4_4") (pintype "passive"))
      (node (ref "U1") (pin "20") (pinfunction "(SCK/PCINT1)_PB1_20") (pintype "bidirectional"))
    )
    (net (code "70") (name "TR1") (class "Default")
      (node (ref "R4_100E") (pin "2") (pinfunction "2_2") (pintype "passive"))
      (node (ref "U1") (pin "53") (pinfunction "PC0_(A8)_53") (pintype "bidirectional"))
    )
    (net (code "71") (name "TR2") (class "Default")
      (node (ref "R6_100E") (pin "2") (pinfunction "2_2") (pintype "passive"))
      (node (ref "U1") (pin "54") (pinfunction "PC1_(A9)_54") (pintype "bidirectional"))
    )
    (net (code "72") (name "TR3") (class "Default")
      (node (ref "R8_100E") (pin "2") (pinfunction "2_2") (pintype "passive"))
      (node (ref "U1") (pin "55") (pinfunction "PC2_(A10)_55") (pintype "bidirectional"))
    )
    (net (code "73") (name "TR4") (class "Default")
      (node (ref "R10_100E") (pin "2") (pinfunction "2_2") (pintype "passive"))
      (node (ref "U1") (pin "56") (pinfunction "PC3_(A11)_56") (pintype "bidirectional"))
    )
    (net (code "74") (name "TR5") (class "Default")
      (node (ref "R12_100E") (pin "2") (pinfunction "2_2") (pintype "passive"))
      (node (ref "U1") (pin "57") (pinfunction "PC4_(A12)_57") (pintype "bidirectional"))
    )
    (net (code "75") (name "TR6") (class "Default")
      (node (ref "R14_100E") (pin "2") (pinfunction "2_2") (pintype "passive"))
      (node (ref "U1") (pin "58") (pinfunction "PC5_(A13)_58") (pintype "bidirectional"))
    )
    (net (code "76") (name "TR7") (class "Default")
      (node (ref "R16_100E") (pin "2") (pinfunction "2_2") (pintype "passive"))
      (node (ref "U1") (pin "59") (pinfunction "PC6_(A14)_59") (pintype "bidirectional"))
    )
    (net (code "77") (name "TR8") (class "Default")
      (node (ref "R18_100E") (pin "2") (pinfunction "2_2") (pintype "passive"))
      (node (ref "U1") (pin "60") (pinfunction "PC7_(A15)_60") (pintype "bidirectional"))
    )
    (net (code "78") (name "TXD") (class "Default")
      (node (ref "U1") (pin "46") (pinfunction "(TXD1/INT3)_PD3_46") (pintype "bidirectional"))
      (node (ref "XB1") (pin "2") (pinfunction "DOUT_2") (pintype "output"))
    )
    (net (code "79") (name "VCC") (class "Default")
      (node (ref "C2_0.1UF") (pin "1") (pinfunction "1_1") (pintype "passive"))
      (node (ref "C9_0.1UF") (pin "1") (pinfunction "1_1") (pintype "passive"))
      (node (ref "IC1") (pin "16") (pinfunction "VCC1_16") (pintype "power_in"))
      (node (ref "IC2") (pin "2") (pinfunction "VO_2") (pintype "passive"))
      (node (ref "IC4") (pin "14") (pinfunction "VDD_14") (pintype "power_in"))
      (node (ref "JP3") (pin "2") (pinfunction "2_2") (pintype "passive"))
      (node (ref "R11_10K") (pin "2") (pinfunction "2_2") (pintype "passive"))
      (node (ref "R13_10K") (pin "2") (pinfunction "2_2") (pintype "passive"))
      (node (ref "R15_10K") (pin "2") (pinfunction "2_2") (pintype "passive"))
      (node (ref "R17_10K") (pin "2") (pinfunction "2_2") (pintype "passive"))
      (node (ref "R19_10K") (pin "2") (pinfunction "2_2") (pintype "passive"))
      (node (ref "R1_1K") (pin "1") (pinfunction "1_1") (pintype "passive"))
      (node (ref "R20_330") (pin "2") (pinfunction "2_2") (pintype "passive"))
      (node (ref "R21_1K") (pin "2") (pinfunction "2_2") (pintype "passive"))
      (node (ref "R22_1_330") (pin "2") (pinfunction "2_2") (pintype "passive"))
      (node (ref "R23_1K") (pin "2") (pinfunction "2_2") (pintype "passive"))
      (node (ref "R34_100E") (pin "1") (pinfunction "1_1") (pintype "passive"))
      (node (ref "R5_10K") (pin "2") (pinfunction "2_2") (pintype "passive"))
      (node (ref "R7_10K") (pin "2") (pinfunction "2_2") (pintype "passive"))
      (node (ref "R9_\\10K") (pin "2") (pinfunction "2_2") (pintype "passive"))
      (node (ref "SV1") (pin "9") (pinfunction "9_9") (pintype "passive"))
      (node (ref "U1") (pin "10") (pinfunction "VCC_3_10") (pintype "power_in"))
      (node (ref "U1") (pin "100") (pinfunction "AVCC_100") (pintype "power_in"))
      (node (ref "U1") (pin "31") (pinfunction "VCC_2_31") (pintype "power_in"))
      (node (ref "U1") (pin "61") (pinfunction "VCC_4_61") (pintype "power_in"))
      (node (ref "U1") (pin "80") (pinfunction "VCC_80") (pintype "power_in"))
      (node (ref "U1") (pin "98") (pinfunction "AREF_98") (pintype "input"))
    )
    (net (code "80") (name "VCC_3.3") (class "Default")
      (node (ref "C10_0.1UF") (pin "1") (pinfunction "1_1") (pintype "passive"))
      (node (ref "IC3") (pin "3") (pinfunction "VO_3") (pintype "passive"))
      (node (ref "R36_10K2") (pin "1") (pinfunction "1_1") (pintype "passive"))
      (node (ref "XB1") (pin "1") (pinfunction "VCC_1") (pintype "power_in"))
      (node (ref "XB1") (pin "14") (pinfunction "VREF_14") (pintype "input"))
    )
    (net (code "81") (name "V_BATT") (class "Default")
      (node (ref "C1_1000UF") (pin "1") (pinfunction "1_1") (pintype "passive"))
      (node (ref "C1_1000UF1") (pin "1") (pinfunction "1_1") (pintype "passive"))
      (node (ref "C3_10UF") (pin "1") (pinfunction "1_1") (pintype "passive"))
      (node (ref "IC1") (pin "8") (pinfunction "VCC2_8") (pintype "power_in"))
      (node (ref "IC2") (pin "1") (pinfunction "VI_1") (pintype "input"))
      (node (ref "IC3") (pin "1") (pinfunction "VI_1") (pintype "input"))
      (node (ref "R2_22K") (pin "2") (pinfunction "2_2") (pintype "passive"))
    )
    (net (code "82") (name "unconnected-(JP3-Pad3)") (class "Default")
      (node (ref "JP3") (pin "3") (pinfunction "3_3") (pintype "passive"))
    )
    (net (code "83") (name "unconnected-(JP3-Pad7)") (class "Default")
      (node (ref "JP3") (pin "7") (pinfunction "7_7") (pintype "passive"))
    )
    (net (code "84") (name "unconnected-(JP3-Pad8)") (class "Default")
      (node (ref "JP3") (pin "8") (pinfunction "8_8") (pintype "passive"))
    )
    (net (code "85") (name "unconnected-(JP3-Pad9)") (class "Default")
      (node (ref "JP3") (pin "9") (pinfunction "9_9") (pintype "passive"))
    )
    (net (code "86") (name "unconnected-(JP3-Pad10)") (class "Default")
      (node (ref "JP3") (pin "10") (pinfunction "10_10") (pintype "passive"))
    )
    (net (code "87") (name "unconnected-(SV1-Pad8)") (class "Default")
      (node (ref "SV1") (pin "8") (pinfunction "8_8") (pintype "passive"))
    )
    (net (code "88") (name "unconnected-(U1-(CLKO{slash}ICP3{slash}INT7)_PE7-Pad9)") (class "Default")
      (node (ref "U1") (pin "9") (pinfunction "(CLKO/ICP3/INT7)_PE7_9") (pintype "bidirectional"))
    )
    (net (code "89") (name "unconnected-(U1-(ICP1)_PD4-Pad47)") (class "Default")
      (node (ref "U1") (pin "47") (pinfunction "(ICP1)_PD4_47") (pintype "bidirectional"))
    )
    (net (code "90") (name "unconnected-(U1-(OC0A{slash}OC1C{slash}PCINT7)_PB7-Pad26)") (class "Default")
      (node (ref "U1") (pin "26") (pinfunction "(OC0A/OC1C/PCINT7)_PB7_26") (pintype "bidirectional"))
    )
    (net (code "91") (name "unconnected-(U1-(OC0B)_PG5-Pad1)") (class "Default")
      (node (ref "U1") (pin "1") (pinfunction "(OC0B)_PG5_1") (pintype "bidirectional"))
    )
    (net (code "92") (name "unconnected-(U1-(OC1A{slash}PCINT5)_PB5-Pad24)") (class "Default")
      (node (ref "U1") (pin "24") (pinfunction "(OC1A/PCINT5)_PB5_24") (pintype "bidirectional"))
    )
    (net (code "93") (name "unconnected-(U1-(OC1B{slash}PCINT6)_PB6-Pad25)") (class "Default")
      (node (ref "U1") (pin "25") (pinfunction "(OC1B/PCINT6)_PB6_25") (pintype "bidirectional"))
    )
    (net (code "94") (name "unconnected-(U1-(OC2A{slash}PCINT4)_PB4-Pad23)") (class "Default")
      (node (ref "U1") (pin "23") (pinfunction "(OC2A/PCINT4)_PB4_23") (pintype "bidirectional"))
    )
    (net (code "95") (name "unconnected-(U1-(OC3A{slash}AIN1)_PE3-Pad5)") (class "Default")
      (node (ref "U1") (pin "5") (pinfunction "(OC3A/AIN1)_PE3_5") (pintype "bidirectional"))
    )
    (net (code "96") (name "unconnected-(U1-(OC3B{slash}INT4)_PE4-Pad6)") (class "Default")
      (node (ref "U1") (pin "6") (pinfunction "(OC3B/INT4)_PE4_6") (pintype "bidirectional"))
    )
    (net (code "97") (name "unconnected-(U1-(OC3C{slash}INT5)_PE5-Pad7)") (class "Default")
      (node (ref "U1") (pin "7") (pinfunction "(OC3C/INT5)_PE5_7") (pintype "bidirectional"))
    )
    (net (code "98") (name "unconnected-(U1-(RXD0{slash}PCINT8)_PE0-Pad2)") (class "Default")
      (node (ref "U1") (pin "2") (pinfunction "(RXD0/PCINT8)_PE0_2") (pintype "bidirectional"))
    )
    (net (code "99") (name "unconnected-(U1-(T0)_PD7-Pad50)") (class "Default")
      (node (ref "U1") (pin "50") (pinfunction "(T0)_PD7_50") (pintype "bidirectional"))
    )
    (net (code "100") (name "unconnected-(U1-(T1)_PD6-Pad49)") (class "Default")
      (node (ref "U1") (pin "49") (pinfunction "(T1)_PD6_49") (pintype "bidirectional"))
    )
    (net (code "101") (name "unconnected-(U1-(T3{slash}INT6)_PE6-Pad8)") (class "Default")
      (node (ref "U1") (pin "8") (pinfunction "(T3/INT6)_PE6_8") (pintype "bidirectional"))
    )
    (net (code "102") (name "unconnected-(U1-(T4)_PH7-Pad27)") (class "Default")
      (node (ref "U1") (pin "27") (pinfunction "(T4)_PH7_27") (pintype "bidirectional"))
    )
    (net (code "103") (name "unconnected-(U1-(TOSC1)_PG4-Pad29)") (class "Default")
      (node (ref "U1") (pin "29") (pinfunction "(TOSC1)_PG4_29") (pintype "bidirectional"))
    )
    (net (code "104") (name "unconnected-(U1-(TOSC2)_PG3-Pad28)") (class "Default")
      (node (ref "U1") (pin "28") (pinfunction "(TOSC2)_PG3_28") (pintype "bidirectional"))
    )
    (net (code "105") (name "unconnected-(U1-(TXD0)_PE1-Pad3)") (class "Default")
      (node (ref "U1") (pin "3") (pinfunction "(TXD0)_PE1_3") (pintype "bidirectional"))
    )
    (net (code "106") (name "unconnected-(U1-(XCK0{slash}AIN0)_PE2-Pad4)") (class "Default")
      (node (ref "U1") (pin "4") (pinfunction "(XCK0/AIN0)_PE2_4") (pintype "bidirectional"))
    )
    (net (code "107") (name "unconnected-(U1-(XCK1)_PD5-Pad48)") (class "Default")
      (node (ref "U1") (pin "48") (pinfunction "(XCK1)_PD5_48") (pintype "bidirectional"))
    )
    (net (code "108") (name "unconnected-(U1-(~{SS{slash}PCINT0})_PB0-Pad19)") (class "Default")
      (node (ref "U1") (pin "19") (pinfunction "(~{SS/PCINT0})_PB0_19") (pintype "bidirectional"))
    )
    (net (code "109") (name "unconnected-(U1-PF0_(ADC0)-Pad97)") (class "Default")
      (node (ref "U1") (pin "97") (pinfunction "PF0_(ADC0)_97") (pintype "bidirectional"))
    )
    (net (code "110") (name "unconnected-(U1-PF1_(ADC1)-Pad96)") (class "Default")
      (node (ref "U1") (pin "96") (pinfunction "PF1_(ADC1)_96") (pintype "bidirectional"))
    )
    (net (code "111") (name "unconnected-(U1-PF2_(ADC2)-Pad95)") (class "Default")
      (node (ref "U1") (pin "95") (pinfunction "PF2_(ADC2)_95") (pintype "bidirectional"))
    )
    (net (code "112") (name "unconnected-(U1-PF3_(ADC3)-Pad94)") (class "Default")
      (node (ref "U1") (pin "94") (pinfunction "PF3_(ADC3)_94") (pintype "bidirectional"))
    )
    (net (code "113") (name "unconnected-(U1-PF4_(ADC4{slash}TCK)-Pad93)") (class "Default")
      (node (ref "U1") (pin "93") (pinfunction "PF4_(ADC4/TCK)_93") (pintype "bidirectional"))
    )
    (net (code "114") (name "unconnected-(U1-PF5_(ADC5{slash}TMS)-Pad92)") (class "Default")
      (node (ref "U1") (pin "92") (pinfunction "PF5_(ADC5/TMS)_92") (pintype "bidirectional"))
    )
    (net (code "115") (name "unconnected-(U1-PF6_(ADC6{slash}TDO)-Pad91)") (class "Default")
      (node (ref "U1") (pin "91") (pinfunction "PF6_(ADC6/TDO)_91") (pintype "bidirectional"))
    )
    (net (code "116") (name "unconnected-(U1-PF7_(ADC7{slash}TDI)-Pad90)") (class "Default")
      (node (ref "U1") (pin "90") (pinfunction "PF7_(ADC7/TDI)_90") (pintype "bidirectional"))
    )
    (net (code "117") (name "unconnected-(U1-PG0_(~{WR})-Pad51)") (class "Default")
      (node (ref "U1") (pin "51") (pinfunction "PG0_(~{WR})_51") (pintype "bidirectional"))
    )
    (net (code "118") (name "unconnected-(U1-PG1_(~{RD})-Pad52)") (class "Default")
      (node (ref "U1") (pin "52") (pinfunction "PG1_(~{RD})_52") (pintype "bidirectional"))
    )
    (net (code "119") (name "unconnected-(U1-PG2_(ALE)-Pad70)") (class "Default")
      (node (ref "U1") (pin "70") (pinfunction "PG2_(ALE)_70") (pintype "bidirectional"))
    )
    (net (code "120") (name "unconnected-(U1-PJ0_(RXD3{slash}PCINT9)-Pad63)") (class "Default")
      (node (ref "U1") (pin "63") (pinfunction "PJ0_(RXD3/PCINT9)_63") (pintype "bidirectional"))
    )
    (net (code "121") (name "unconnected-(U1-PJ1_(TXD3{slash}PCINT10)-Pad64)") (class "Default")
      (node (ref "U1") (pin "64") (pinfunction "PJ1_(TXD3/PCINT10)_64") (pintype "bidirectional"))
    )
    (net (code "122") (name "unconnected-(U1-PJ2_(XCK3{slash}PCINT11)-Pad65)") (class "Default")
      (node (ref "U1") (pin "65") (pinfunction "PJ2_(XCK3/PCINT11)_65") (pintype "bidirectional"))
    )
    (net (code "123") (name "unconnected-(U1-PJ3_(PCINT12)-Pad66)") (class "Default")
      (node (ref "U1") (pin "66") (pinfunction "PJ3_(PCINT12)_66") (pintype "bidirectional"))
    )
    (net (code "124") (name "unconnected-(U1-PJ4_(PCINT13)-Pad67)") (class "Default")
      (node (ref "U1") (pin "67") (pinfunction "PJ4_(PCINT13)_67") (pintype "bidirectional"))
    )
    (net (code "125") (name "unconnected-(U1-PJ5_(PCINT14)-Pad68)") (class "Default")
      (node (ref "U1") (pin "68") (pinfunction "PJ5_(PCINT14)_68") (pintype "bidirectional"))
    )
    (net (code "126") (name "unconnected-(U1-PJ6_(PCINT15)-Pad69)") (class "Default")
      (node (ref "U1") (pin "69") (pinfunction "PJ6_(PCINT15)_69") (pintype "bidirectional"))
    )
    (net (code "127") (name "unconnected-(U1-PJ7-Pad79)") (class "Default")
      (node (ref "U1") (pin "79") (pinfunction "PJ7_79") (pintype "bidirectional"))
    )
    (net (code "128") (name "unconnected-(U1-PK0_(ADC8{slash}PCINT16)-Pad89)") (class "Default")
      (node (ref "U1") (pin "89") (pinfunction "PK0_(ADC8/PCINT16)_89") (pintype "bidirectional"))
    )
    (net (code "129") (name "unconnected-(U1-PK1_(ADC9{slash}PCINT17)-Pad88)") (class "Default")
      (node (ref "U1") (pin "88") (pinfunction "PK1_(ADC9/PCINT17)_88") (pintype "bidirectional"))
    )
    (net (code "130") (name "unconnected-(U1-PK2_(ADC10{slash}PCINT18)-Pad87)") (class "Default")
      (node (ref "U1") (pin "87") (pinfunction "PK2_(ADC10/PCINT18)_87") (pintype "bidirectional"))
    )
    (net (code "131") (name "unconnected-(U1-PK3_(ADC11{slash}PCINT19)-Pad86)") (class "Default")
      (node (ref "U1") (pin "86") (pinfunction "PK3_(ADC11/PCINT19)_86") (pintype "bidirectional"))
    )
    (net (code "132") (name "unconnected-(U1-PK4_(ADC12{slash}PCINT20)-Pad85)") (class "Default")
      (node (ref "U1") (pin "85") (pinfunction "PK4_(ADC12/PCINT20)_85") (pintype "bidirectional"))
    )
    (net (code "133") (name "unconnected-(U1-PK5_(ADC13{slash}PCINT21)-Pad84)") (class "Default")
      (node (ref "U1") (pin "84") (pinfunction "PK5_(ADC13/PCINT21)_84") (pintype "bidirectional"))
    )
    (net (code "134") (name "unconnected-(U1-PK6_(ADC14{slash}PCINT22)-Pad83)") (class "Default")
      (node (ref "U1") (pin "83") (pinfunction "PK6_(ADC14/PCINT22)_83") (pintype "bidirectional"))
    )
    (net (code "135") (name "unconnected-(U1-PK7_(ADC15{slash}PCINT23)-Pad82)") (class "Default")
      (node (ref "U1") (pin "82") (pinfunction "PK7_(ADC15/PCINT23)_82") (pintype "bidirectional"))
    )
    (net (code "136") (name "unconnected-(U1-PL6-Pad41)") (class "Default")
      (node (ref "U1") (pin "41") (pinfunction "PL6_41") (pintype "bidirectional"))
    )
    (net (code "137") (name "unconnected-(U1-PL7-Pad42)") (class "Default")
      (node (ref "U1") (pin "42") (pinfunction "PL7_42") (pintype "bidirectional"))
    )
    (net (code "138") (name "unconnected-(XB1-AD0{slash}DIO0-Pad20)") (class "Default")
      (node (ref "XB1") (pin "20") (pinfunction "AD0/DIO0_20") (pintype "bidirectional"))
    )
    (net (code "139") (name "unconnected-(XB1-AD1{slash}DIO1-Pad19)") (class "Default")
      (node (ref "XB1") (pin "19") (pinfunction "AD1/DIO1_19") (pintype "bidirectional"))
    )
    (net (code "140") (name "unconnected-(XB1-AD2{slash}DIO2-Pad18)") (class "Default")
      (node (ref "XB1") (pin "18") (pinfunction "AD2/DIO2_18") (pintype "bidirectional"))
    )
    (net (code "141") (name "unconnected-(XB1-AD3{slash}DIO3-Pad17)") (class "Default")
      (node (ref "XB1") (pin "17") (pinfunction "AD3/DIO3_17") (pintype "bidirectional"))
    )
    (net (code "142") (name "unconnected-(XB1-DIO4-Pad11)") (class "Default")
      (node (ref "XB1") (pin "11") (pinfunction "DIO4_11") (pintype "bidirectional"))
    )
    (net (code "143") (name "unconnected-(XB1-DIO12-Pad4)") (class "Default")
      (node (ref "XB1") (pin "4") (pinfunction "DIO12_4") (pintype "bidirectional"))
    )
    (net (code "144") (name "unconnected-(XB1-ON{slash}~{SLEEP}-Pad13)") (class "Default")
      (node (ref "XB1") (pin "13") (pinfunction "ON/~{SLEEP}_13") (pintype "output"))
    )
    (net (code "145") (name "unconnected-(XB1-~{CTS}{slash}DIO7-Pad12)") (class "Default")
      (node (ref "XB1") (pin "12") (pinfunction "~{CTS}/DIO7_12") (pintype "bidirectional"))
    )
    (net (code "146") (name "unconnected-(XB1-~{DTR}{slash}SLEEP_RQ{slash}DIO8-Pad9)") (class "Default")
      (node (ref "XB1") (pin "9") (pinfunction "~{DTR}/SLEEP_RQ/DIO8_9") (pintype "bidirectional"))
    )
    (net (code "147") (name "unconnected-(XB1-~{RESET}-Pad5)") (class "Default")
      (node (ref "XB1") (pin "5") (pinfunction "~{RESET}_5") (pintype "input"))
    )
    (net (code "148") (name "unconnected-(XB1-~{RTS}{slash}DIO6-Pad16)") (class "Default")
      (node (ref "XB1") (pin "16") (pinfunction "~{RTS}/DIO6_16") (pintype "bidirectional"))
    )
  )
)
